# sauroneye.net
KiCad netlist of a schematic drawn in EAGLE
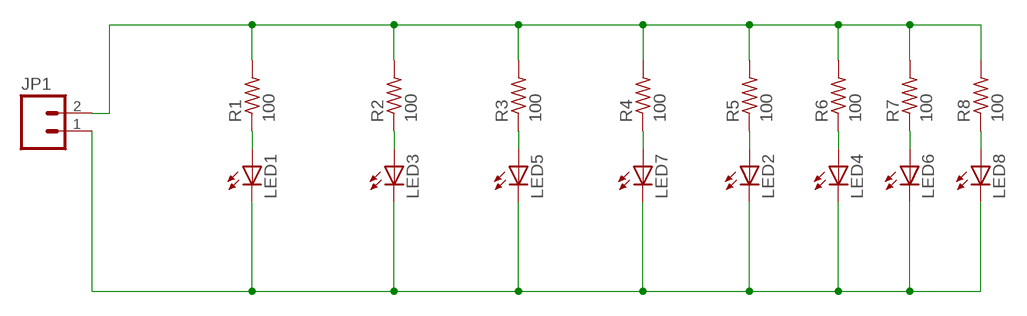
[diagram p0: schematic, sheet 1]

(export (version "E")
  (design (tool "Eeschema 10.0.6"))
  (components
    (comp (ref "JP1")
      (value "M02PTH")
      (footprint "eagle-import:1X02")
      (libsource (lib "eagle-import") (part "M02PTH"))
    )
    (comp (ref "LED1")
      (value "LEDCHIP-LED0805")
      (footprint "eagle-import:CHIP-LED0805")
      (libsource (lib "eagle-import") (part "LEDCHIP-LED0805"))
    )
    (comp (ref "LED2")
      (value "LEDCHIP-LED0805")
      (footprint "eagle-import:CHIP-LED0805")
      (libsource (lib "eagle-import") (part "LEDCHIP-LED0805"))
    )
    (comp (ref "LED3")
      (value "LEDCHIP-LED0805")
      (footprint "eagle-import:CHIP-LED0805")
      (libsource (lib "eagle-import") (part "LEDCHIP-LED0805"))
    )
    (comp (ref "LED4")
      (value "LEDCHIP-LED0805")
      (footprint "eagle-import:CHIP-LED0805")
      (libsource (lib "eagle-import") (part "LEDCHIP-LED0805"))
    )
    (comp (ref "LED5")
      (value "LEDCHIP-LED0805")
      (footprint "eagle-import:CHIP-LED0805")
      (libsource (lib "eagle-import") (part "LEDCHIP-LED0805"))
    )
    (comp (ref "LED6")
      (value "LEDCHIP-LED0805")
      (footprint "eagle-import:CHIP-LED0805")
      (libsource (lib "eagle-import") (part "LEDCHIP-LED0805"))
    )
    (comp (ref "LED7")
      (value "LEDCHIP-LED0805")
      (footprint "eagle-import:CHIP-LED0805")
      (libsource (lib "eagle-import") (part "LEDCHIP-LED0805"))
    )
    (comp (ref "LED8")
      (value "LEDCHIP-LED0805")
      (footprint "eagle-import:CHIP-LED0805")
      (libsource (lib "eagle-import") (part "LEDCHIP-LED0805"))
    )
    (comp (ref "R1")
      (value "100")
      (footprint "eagle-import:R0805")
      (libsource (lib "eagle-import") (part "R-US_R0805"))
    )
    (comp (ref "R2")
      (value "100")
      (footprint "eagle-import:R0805")
      (libsource (lib "eagle-import") (part "R-US_R0805"))
    )
    (comp (ref "R3")
      (value "100")
      (footprint "eagle-import:R0805")
      (libsource (lib "eagle-import") (part "R-US_R0805"))
    )
    (comp (ref "R4")
      (value "100")
      (footprint "eagle-import:R0805")
      (libsource (lib "eagle-import") (part "R-US_R0805"))
    )
    (comp (ref "R5")
      (value "100")
      (footprint "eagle-import:R0805")
      (libsource (lib "eagle-import") (part "R-US_R0805"))
    )
    (comp (ref "R6")
      (value "100")
      (footprint "eagle-import:R0805")
      (libsource (lib "eagle-import") (part "R-US_R0805"))
    )
    (comp (ref "R7")
      (value "100")
      (footprint "eagle-import:R0805")
      (libsource (lib "eagle-import") (part "R-US_R0805"))
    )
    (comp (ref "R8")
      (value "100")
      (footprint "eagle-import:R0805")
      (libsource (lib "eagle-import") (part "R-US_R0805"))
    )
  )
  (nets
    (net (code "1") (name "Net-(JP1-Pad1)") (class "Default")
      (node (ref "JP1") (pin "1") (pinfunction "1_1") (pintype "passive"))
      (node (ref "LED1") (pin "C") (pinfunction "C_C") (pintype "passive"))
      (node (ref "LED2") (pin "C") (pinfunction "C_C") (pintype "passive"))
      (node (ref "LED3") (pin "C") (pinfunction "C_C") (pintype "passive"))
      (node (ref "LED4") (pin "C") (pinfunction "C_C") (pintype "passive"))
      (node (ref "LED5") (pin "C") (pinfunction "C_C") (pintype "passive"))
      (node (ref "LED6") (pin "C") (pinfunction "C_C") (pintype "passive"))
      (node (ref "LED7") (pin "C") (pinfunction "C_C") (pintype "passive"))
      (node (ref "LED8") (pin "C") (pinfunction "C_C") (pintype "passive"))
    )
    (net (code "2") (name "Net-(JP1-Pad2)") (class "Default")
      (node (ref "JP1") (pin "2") (pinfunction "2_2") (pintype "passive"))
      (node (ref "R1") (pin "2") (pinfunction "2_2") (pintype "passive"))
      (node (ref "R2") (pin "2") (pinfunction "2_2") (pintype "passive"))
      (node (ref "R3") (pin "2") (pinfunction "2_2") (pintype "passive"))
      (node (ref "R4") (pin "2") (pinfunction "2_2") (pintype "passive"))
      (node (ref "R5") (pin "2") (pinfunction "2_2") (pintype "passive"))
      (node (ref "R6") (pin "2") (pinfunction "2_2") (pintype "passive"))
      (node (ref "R7") (pin "2") (pinfunction "2_2") (pintype "passive"))
      (node (ref "R8") (pin "2") (pinfunction "2_2") (pintype "passive"))
    )
    (net (code "3") (name "Net-(LED1-PadA)") (class "Default")
      (node (ref "LED1") (pin "A") (pinfunction "A_A") (pintype "passive"))
      (node (ref "R1") (pin "1") (pinfunction "1_1") (pintype "passive"))
    )
    (net (code "4") (name "Net-(LED2-PadA)") (class "Default")
      (node (ref "LED2") (pin "A") (pinfunction "A_A") (pintype "passive"))
      (node (ref "R5") (pin "1") (pinfunction "1_1") (pintype "passive"))
    )
    (net (code "5") (name "Net-(LED3-PadA)") (class "Default")
      (node (ref "LED3") (pin "A") (pinfunction "A_A") (pintype "passive"))
      (node (ref "R2") (pin "1") (pinfunction "1_1") (pintype "passive"))
    )
    (net (code "6") (name "Net-(LED4-PadA)") (class "Default")
      (node (ref "LED4") (pin "A") (pinfunction "A_A") (pintype "passive"))
      (node (ref "R6") (pin "1") (pinfunction "1_1") (pintype "passive"))
    )
    (net (code "7") (name "Net-(LED5-PadA)") (class "Default")
      (node (ref "LED5") (pin "A") (pinfunction "A_A") (pintype "passive"))
      (node (ref "R3") (pin "1") (pinfunction "1_1") (pintype "passive"))
    )
    (net (code "8") (name "Net-(LED6-PadA)") (class "Default")
      (node (ref "LED6") (pin "A") (pinfunction "A_A") (pintype "passive"))
      (node (ref "R7") (pin "1") (pinfunction "1_1") (pintype "passive"))
    )
    (net (code "9") (name "Net-(LED7-PadA)") (class "Default")
      (node (ref "LED7") (pin "A") (pinfunction "A_A") (pintype "passive"))
      (node (ref "R4") (pin "1") (pinfunction "1_1") (pintype "passive"))
    )
    (net (code "10") (name "Net-(LED8-PadA)") (class "Default")
      (node (ref "LED8") (pin "A") (pinfunction "A_A") (pintype "passive"))
      (node (ref "R8") (pin "1") (pinfunction "1_1") (pintype "passive"))
    )
  )
)
